# LEDs.net
KiCad netlist of a schematic drawn in Altium Designer
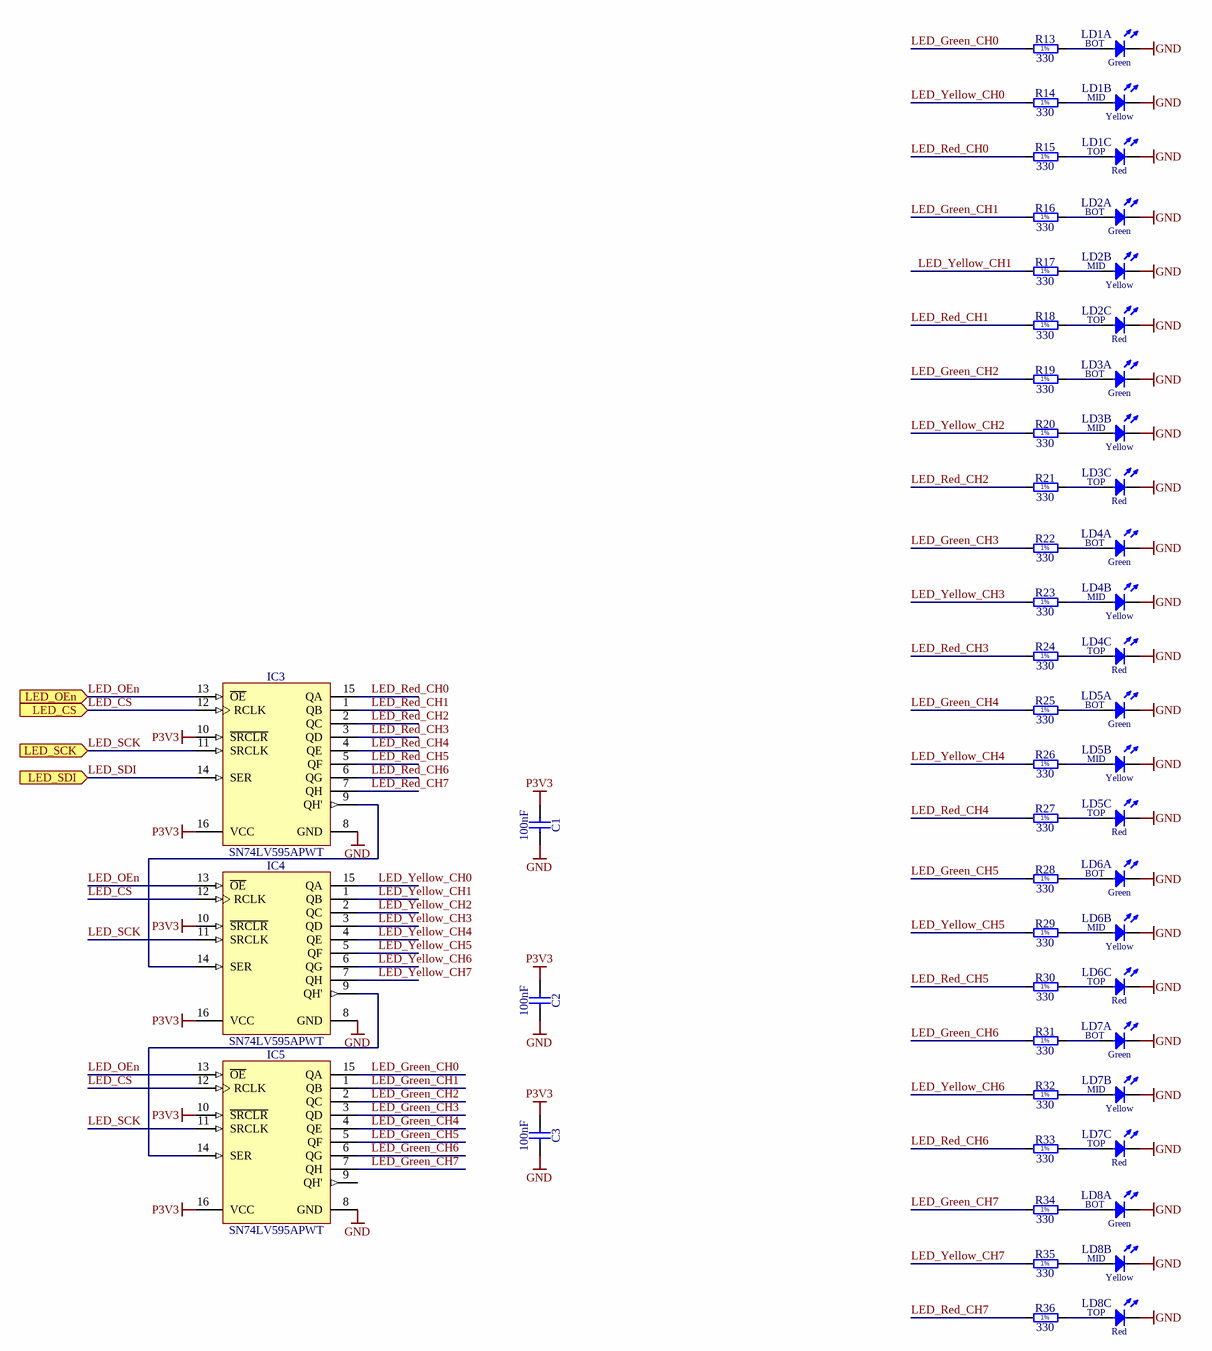
[diagram p0: LEDs.SchDoc]

(export (version "E")
  (design (tool "Eeschema 10.0.6"))
  (components
    (comp (ref "C1")
      (value "100nF")
      (footprint "CAPC1005X55N")
      (description "Non-polarised capacitor")
      (fields
        (field (name "PART NUMBER") "CC0402_100NF_16V_10%_X7R")
        (field (name "VOLTAGE") "16V")
        (field (name "AUTHOR") "CERN DEM JLC")
      )
      (libsource (lib "Capacitors") (part "Capacitor - non polarized"))
    )
    (comp (ref "C2")
      (value "100nF")
      (footprint "CAPC1005X55N")
      (description "Non-polarised capacitor")
      (fields
        (field (name "PART NUMBER") "CC0402_100NF_16V_10%_X7R")
        (field (name "VOLTAGE") "16V")
        (field (name "AUTHOR") "CERN DEM JLC")
      )
      (libsource (lib "Capacitors") (part "Capacitor - non polarized"))
    )
    (comp (ref "C3")
      (value "100nF")
      (footprint "CAPC1005X55N")
      (description "Non-polarised capacitor")
      (fields
        (field (name "PART NUMBER") "CC0402_100NF_16V_10%_X7R")
        (field (name "VOLTAGE") "16V")
        (field (name "AUTHOR") "CERN DEM JLC")
      )
      (libsource (lib "Capacitors") (part "Capacitor - non polarized"))
    )
    (comp (ref "IC3")
      (value "SN74LV595APWT")
      (footprint "SOP65P640X120-16N")
      (description "8-Bit Shift Register With 3-State Output Register")
      (fields (field (name "MANUFACTURER") "TEXAS INSTRUMENTS") (field (name "AUTHOR") "CERN DEM JLC"))
      (libsource (lib "ICs And Semiconductors") (part "74595"))
    )
    (comp (ref "IC4")
      (value "SN74LV595APWT")
      (footprint "SOP65P640X120-16N")
      (description "8-Bit Shift Register With 3-State Output Register")
      (fields (field (name "MANUFACTURER") "TEXAS INSTRUMENTS") (field (name "AUTHOR") "CERN DEM JLC"))
      (libsource (lib "ICs And Semiconductors") (part "74595"))
    )
    (comp (ref "IC5")
      (value "SN74LV595APWT")
      (footprint "SOP65P640X120-16N")
      (description "8-Bit Shift Register With 3-State Output Register")
      (fields (field (name "MANUFACTURER") "TEXAS INSTRUMENTS") (field (name "AUTHOR") "CERN DEM JLC"))
      (libsource (lib "ICs And Semiconductors") (part "74595"))
    )
    (comp (ref "LD1")
      (value "Red/Yellow/Green")
      (footprint "LED_MENTOR_1882.2781")
      (description "LED x3 G-1C2A-BOT_Y-3C4A_R-5C6A-TOP")
      (fields
        (field (name "PART NUMBER") "LED_MENTOR_1882.2781")
        (field (name "MANUFACTURER") "MENTOR")
        (field (name "AUTHOR") "CERN DEM JLC")
      )
      (libsource (lib "ICs And Semiconductors") (part "LED x3 G-1C2A-BOT_Y-3C4A_R-5C6A-TOP"))
    )
    (comp (ref "LD2")
      (value "Red/Yellow/Green")
      (footprint "LED_MENTOR_1882.2781")
      (description "LED x3 G-1C2A-BOT_Y-3C4A_R-5C6A-TOP")
      (fields
        (field (name "PART NUMBER") "LED_MENTOR_1882.2781")
        (field (name "MANUFACTURER") "MENTOR")
        (field (name "AUTHOR") "CERN DEM JLC")
      )
      (libsource (lib "ICs And Semiconductors") (part "LED x3 G-1C2A-BOT_Y-3C4A_R-5C6A-TOP"))
    )
    (comp (ref "LD3")
      (value "Red/Yellow/Green")
      (footprint "LED_MENTOR_1882.2781")
      (description "LED x3 G-1C2A-BOT_Y-3C4A_R-5C6A-TOP")
      (fields
        (field (name "PART NUMBER") "LED_MENTOR_1882.2781")
        (field (name "MANUFACTURER") "MENTOR")
        (field (name "AUTHOR") "CERN DEM JLC")
      )
      (libsource (lib "ICs And Semiconductors") (part "LED x3 G-1C2A-BOT_Y-3C4A_R-5C6A-TOP"))
    )
    (comp (ref "LD4")
      (value "Red/Yellow/Green")
      (footprint "LED_MENTOR_1882.2781")
      (description "LED x3 G-1C2A-BOT_Y-3C4A_R-5C6A-TOP")
      (fields
        (field (name "PART NUMBER") "LED_MENTOR_1882.2781")
        (field (name "MANUFACTURER") "MENTOR")
        (field (name "AUTHOR") "CERN DEM JLC")
      )
      (libsource (lib "ICs And Semiconductors") (part "LED x3 G-1C2A-BOT_Y-3C4A_R-5C6A-TOP"))
    )
    (comp (ref "LD5")
      (value "Red/Yellow/Green")
      (footprint "LED_MENTOR_1882.2781")
      (description "LED x3 G-1C2A-BOT_Y-3C4A_R-5C6A-TOP")
      (fields
        (field (name "PART NUMBER") "LED_MENTOR_1882.2781")
        (field (name "MANUFACTURER") "MENTOR")
        (field (name "AUTHOR") "CERN DEM JLC")
      )
      (libsource (lib "ICs And Semiconductors") (part "LED x3 G-1C2A-BOT_Y-3C4A_R-5C6A-TOP"))
    )
    (comp (ref "LD6")
      (value "Red/Yellow/Green")
      (footprint "LED_MENTOR_1882.2781")
      (description "LED x3 G-1C2A-BOT_Y-3C4A_R-5C6A-TOP")
      (fields
        (field (name "PART NUMBER") "LED_MENTOR_1882.2781")
        (field (name "MANUFACTURER") "MENTOR")
        (field (name "AUTHOR") "CERN DEM JLC")
      )
      (libsource (lib "ICs And Semiconductors") (part "LED x3 G-1C2A-BOT_Y-3C4A_R-5C6A-TOP"))
    )
    (comp (ref "LD7")
      (value "Red/Yellow/Green")
      (footprint "LED_MENTOR_1882.2781")
      (description "LED x3 G-1C2A-BOT_Y-3C4A_R-5C6A-TOP")
      (fields
        (field (name "PART NUMBER") "LED_MENTOR_1882.2781")
        (field (name "MANUFACTURER") "MENTOR")
        (field (name "AUTHOR") "CERN DEM JLC")
      )
      (libsource (lib "ICs And Semiconductors") (part "LED x3 G-1C2A-BOT_Y-3C4A_R-5C6A-TOP"))
    )
    (comp (ref "LD8")
      (value "Red/Yellow/Green")
      (footprint "LED_MENTOR_1882.2781")
      (description "LED x3 G-1C2A-BOT_Y-3C4A_R-5C6A-TOP")
      (fields
        (field (name "PART NUMBER") "LED_MENTOR_1882.2781")
        (field (name "MANUFACTURER") "MENTOR")
        (field (name "AUTHOR") "CERN DEM JLC")
      )
      (libsource (lib "ICs And Semiconductors") (part "LED x3 G-1C2A-BOT_Y-3C4A_R-5C6A-TOP"))
    )
    (comp (ref "R13")
      (value "330")
      (footprint "RESC1608X55N")
      (description "Resistor - 1%")
      (fields
        (field (name "PART NUMBER") "R0603_330R_1%_0.1W_100PPM")
        (field (name "POWER") "0.1W")
        (field (name "AUTHOR") "CERN DEM JLC")
      )
      (libsource (lib "Resistors") (part "Resistor - 1%"))
    )
    (comp (ref "R14")
      (value "330")
      (footprint "RESC1608X55N")
      (description "Resistor - 1%")
      (fields
        (field (name "PART NUMBER") "R0603_330R_1%_0.1W_100PPM")
        (field (name "POWER") "0.1W")
        (field (name "AUTHOR") "CERN DEM JLC")
      )
      (libsource (lib "Resistors") (part "Resistor - 1%"))
    )
    (comp (ref "R15")
      (value "330")
      (footprint "RESC1608X55N")
      (description "Resistor - 1%")
      (fields
        (field (name "PART NUMBER") "R0603_330R_1%_0.1W_100PPM")
        (field (name "POWER") "0.1W")
        (field (name "AUTHOR") "CERN DEM JLC")
      )
      (libsource (lib "Resistors") (part "Resistor - 1%"))
    )
    (comp (ref "R16")
      (value "330")
      (footprint "RESC1608X55N")
      (description "Resistor - 1%")
      (fields
        (field (name "PART NUMBER") "R0603_330R_1%_0.1W_100PPM")
        (field (name "POWER") "0.1W")
        (field (name "AUTHOR") "CERN DEM JLC")
      )
      (libsource (lib "Resistors") (part "Resistor - 1%"))
    )
    (comp (ref "R17")
      (value "330")
      (footprint "RESC1608X55N")
      (description "Resistor - 1%")
      (fields
        (field (name "PART NUMBER") "R0603_330R_1%_0.1W_100PPM")
        (field (name "POWER") "0.1W")
        (field (name "AUTHOR") "CERN DEM JLC")
      )
      (libsource (lib "Resistors") (part "Resistor - 1%"))
    )
    (comp (ref "R18")
      (value "330")
      (footprint "RESC1608X55N")
      (description "Resistor - 1%")
      (fields
        (field (name "PART NUMBER") "R0603_330R_1%_0.1W_100PPM")
        (field (name "POWER") "0.1W")
        (field (name "AUTHOR") "CERN DEM JLC")
      )
      (libsource (lib "Resistors") (part "Resistor - 1%"))
    )
    (comp (ref "R19")
      (value "330")
      (footprint "RESC1608X55N")
      (description "Resistor - 1%")
      (fields
        (field (name "PART NUMBER") "R0603_330R_1%_0.1W_100PPM")
        (field (name "POWER") "0.1W")
        (field (name "AUTHOR") "CERN DEM JLC")
      )
      (libsource (lib "Resistors") (part "Resistor - 1%"))
    )
    (comp (ref "R20")
      (value "330")
      (footprint "RESC1608X55N")
      (description "Resistor - 1%")
      (fields
        (field (name "PART NUMBER") "R0603_330R_1%_0.1W_100PPM")
        (field (name "POWER") "0.1W")
        (field (name "AUTHOR") "CERN DEM JLC")
      )
      (libsource (lib "Resistors") (part "Resistor - 1%"))
    )
    (comp (ref "R21")
      (value "330")
      (footprint "RESC1608X55N")
      (description "Resistor - 1%")
      (fields
        (field (name "PART NUMBER") "R0603_330R_1%_0.1W_100PPM")
        (field (name "POWER") "0.1W")
        (field (name "AUTHOR") "CERN DEM JLC")
      )
      (libsource (lib "Resistors") (part "Resistor - 1%"))
    )
    (comp (ref "R22")
      (value "330")
      (footprint "RESC1608X55N")
      (description "Resistor - 1%")
      (fields
        (field (name "PART NUMBER") "R0603_330R_1%_0.1W_100PPM")
        (field (name "POWER") "0.1W")
        (field (name "AUTHOR") "CERN DEM JLC")
      )
      (libsource (lib "Resistors") (part "Resistor - 1%"))
    )
    (comp (ref "R23")
      (value "330")
      (footprint "RESC1608X55N")
      (description "Resistor - 1%")
      (fields
        (field (name "PART NUMBER") "R0603_330R_1%_0.1W_100PPM")
        (field (name "POWER") "0.1W")
        (field (name "AUTHOR") "CERN DEM JLC")
      )
      (libsource (lib "Resistors") (part "Resistor - 1%"))
    )
    (comp (ref "R24")
      (value "330")
      (footprint "RESC1608X55N")
      (description "Resistor - 1%")
      (fields
        (field (name "PART NUMBER") "R0603_330R_1%_0.1W_100PPM")
        (field (name "POWER") "0.1W")
        (field (name "AUTHOR") "CERN DEM JLC")
      )
      (libsource (lib "Resistors") (part "Resistor - 1%"))
    )
    (comp (ref "R25")
      (value "330")
      (footprint "RESC1608X55N")
      (description "Resistor - 1%")
      (fields
        (field (name "PART NUMBER") "R0603_330R_1%_0.1W_100PPM")
        (field (name "POWER") "0.1W")
        (field (name "AUTHOR") "CERN DEM JLC")
      )
      (libsource (lib "Resistors") (part "Resistor - 1%"))
    )
    (comp (ref "R26")
      (value "330")
      (footprint "RESC1608X55N")
      (description "Resistor - 1%")
      (fields
        (field (name "PART NUMBER") "R0603_330R_1%_0.1W_100PPM")
        (field (name "POWER") "0.1W")
        (field (name "AUTHOR") "CERN DEM JLC")
      )
      (libsource (lib "Resistors") (part "Resistor - 1%"))
    )
    (comp (ref "R27")
      (value "330")
      (footprint "RESC1608X55N")
      (description "Resistor - 1%")
      (fields
        (field (name "PART NUMBER") "R0603_330R_1%_0.1W_100PPM")
        (field (name "POWER") "0.1W")
        (field (name "AUTHOR") "CERN DEM JLC")
      )
      (libsource (lib "Resistors") (part "Resistor - 1%"))
    )
    (comp (ref "R28")
      (value "330")
      (footprint "RESC1608X55N")
      (description "Resistor - 1%")
      (fields
        (field (name "PART NUMBER") "R0603_330R_1%_0.1W_100PPM")
        (field (name "POWER") "0.1W")
        (field (name "AUTHOR") "CERN DEM JLC")
      )
      (libsource (lib "Resistors") (part "Resistor - 1%"))
    )
    (comp (ref "R29")
      (value "330")
      (footprint "RESC1608X55N")
      (description "Resistor - 1%")
      (fields
        (field (name "PART NUMBER") "R0603_330R_1%_0.1W_100PPM")
        (field (name "POWER") "0.1W")
        (field (name "AUTHOR") "CERN DEM JLC")
      )
      (libsource (lib "Resistors") (part "Resistor - 1%"))
    )
    (comp (ref "R30")
      (value "330")
      (footprint "RESC1608X55N")
      (description "Resistor - 1%")
      (fields
        (field (name "PART NUMBER") "R0603_330R_1%_0.1W_100PPM")
        (field (name "POWER") "0.1W")
        (field (name "AUTHOR") "CERN DEM JLC")
      )
      (libsource (lib "Resistors") (part "Resistor - 1%"))
    )
    (comp (ref "R31")
      (value "330")
      (footprint "RESC1608X55N")
      (description "Resistor - 1%")
      (fields
        (field (name "PART NUMBER") "R0603_330R_1%_0.1W_100PPM")
        (field (name "POWER") "0.1W")
        (field (name "AUTHOR") "CERN DEM JLC")
      )
      (libsource (lib "Resistors") (part "Resistor - 1%"))
    )
    (comp (ref "R32")
      (value "330")
      (footprint "RESC1608X55N")
      (description "Resistor - 1%")
      (fields
        (field (name "PART NUMBER") "R0603_330R_1%_0.1W_100PPM")
        (field (name "POWER") "0.1W")
        (field (name "AUTHOR") "CERN DEM JLC")
      )
      (libsource (lib "Resistors") (part "Resistor - 1%"))
    )
    (comp (ref "R33")
      (value "330")
      (footprint "RESC1608X55N")
      (description "Resistor - 1%")
      (fields
        (field (name "PART NUMBER") "R0603_330R_1%_0.1W_100PPM")
        (field (name "POWER") "0.1W")
        (field (name "AUTHOR") "CERN DEM JLC")
      )
      (libsource (lib "Resistors") (part "Resistor - 1%"))
    )
    (comp (ref "R34")
      (value "330")
      (footprint "RESC1608X55N")
      (description "Resistor - 1%")
      (fields
        (field (name "PART NUMBER") "R0603_330R_1%_0.1W_100PPM")
        (field (name "POWER") "0.1W")
        (field (name "AUTHOR") "CERN DEM JLC")
      )
      (libsource (lib "Resistors") (part "Resistor - 1%"))
    )
    (comp (ref "R35")
      (value "330")
      (footprint "RESC1608X55N")
      (description "Resistor - 1%")
      (fields
        (field (name "PART NUMBER") "R0603_330R_1%_0.1W_100PPM")
        (field (name "POWER") "0.1W")
        (field (name "AUTHOR") "CERN DEM JLC")
      )
      (libsource (lib "Resistors") (part "Resistor - 1%"))
    )
    (comp (ref "R36")
      (value "330")
      (footprint "RESC1608X55N")
      (description "Resistor - 1%")
      (fields
        (field (name "PART NUMBER") "R0603_330R_1%_0.1W_100PPM")
        (field (name "POWER") "0.1W")
        (field (name "AUTHOR") "CERN DEM JLC")
      )
      (libsource (lib "Resistors") (part "Resistor - 1%"))
    )
  )
  (nets
    (net (code "1") (name "/LED_CS") (class "Default")
      (node (ref "IC3") (pin "12") (pinfunction "RCLK_12") (pintype "input"))
      (node (ref "IC4") (pin "12") (pinfunction "RCLK_12") (pintype "input"))
      (node (ref "IC5") (pin "12") (pinfunction "RCLK_12") (pintype "input"))
    )
    (net (code "2") (name "/LED_Green_CH0") (class "Default")
      (node (ref "IC5") (pin "15") (pinfunction "QA_15") (pintype "tri_state"))
      (node (ref "R13") (pin "1") (pinfunction "1_1") (pintype "passive"))
    )
    (net (code "3") (name "/LED_Green_CH1") (class "Default")
      (node (ref "IC5") (pin "1") (pinfunction "QB_1") (pintype "tri_state"))
      (node (ref "R16") (pin "1") (pinfunction "1_1") (pintype "passive"))
    )
    (net (code "4") (name "/LED_Green_CH2") (class "Default")
      (node (ref "IC5") (pin "2") (pinfunction "QC_2") (pintype "tri_state"))
      (node (ref "R19") (pin "1") (pinfunction "1_1") (pintype "passive"))
    )
    (net (code "5") (name "/LED_Green_CH3") (class "Default")
      (node (ref "IC5") (pin "3") (pinfunction "QD_3") (pintype "tri_state"))
      (node (ref "R22") (pin "1") (pinfunction "1_1") (pintype "passive"))
    )
    (net (code "6") (name "/LED_Green_CH4") (class "Default")
      (node (ref "IC5") (pin "4") (pinfunction "QE_4") (pintype "tri_state"))
      (node (ref "R25") (pin "1") (pinfunction "1_1") (pintype "passive"))
    )
    (net (code "7") (name "/LED_Green_CH5") (class "Default")
      (node (ref "IC5") (pin "5") (pinfunction "QF_5") (pintype "tri_state"))
      (node (ref "R28") (pin "1") (pinfunction "1_1") (pintype "passive"))
    )
    (net (code "8") (name "/LED_Green_CH6") (class "Default")
      (node (ref "IC5") (pin "6") (pinfunction "QG_6") (pintype "tri_state"))
      (node (ref "R31") (pin "1") (pinfunction "1_1") (pintype "passive"))
    )
    (net (code "9") (name "/LED_Green_CH7") (class "Default")
      (node (ref "IC5") (pin "7") (pinfunction "QH_7") (pintype "tri_state"))
      (node (ref "R34") (pin "1") (pinfunction "1_1") (pintype "passive"))
    )
    (net (code "10") (name "/LED_OEn") (class "Default")
      (node (ref "IC3") (pin "13") (pinfunction "~{OE}_13") (pintype "input"))
      (node (ref "IC4") (pin "13") (pinfunction "~{OE}_13") (pintype "input"))
      (node (ref "IC5") (pin "13") (pinfunction "~{OE}_13") (pintype "input"))
    )
    (net (code "11") (name "/LED_Red_CH0") (class "Default")
      (node (ref "IC3") (pin "15") (pinfunction "QA_15") (pintype "tri_state"))
      (node (ref "R15") (pin "1") (pinfunction "1_1") (pintype "passive"))
    )
    (net (code "12") (name "/LED_Red_CH1") (class "Default")
      (node (ref "IC3") (pin "1") (pinfunction "QB_1") (pintype "tri_state"))
      (node (ref "R18") (pin "1") (pinfunction "1_1") (pintype "passive"))
    )
    (net (code "13") (name "/LED_Red_CH2") (class "Default")
      (node (ref "IC3") (pin "2") (pinfunction "QC_2") (pintype "tri_state"))
      (node (ref "R21") (pin "1") (pinfunction "1_1") (pintype "passive"))
    )
    (net (code "14") (name "/LED_Red_CH3") (class "Default")
      (node (ref "IC3") (pin "3") (pinfunction "QD_3") (pintype "tri_state"))
      (node (ref "R24") (pin "1") (pinfunction "1_1") (pintype "passive"))
    )
    (net (code "15") (name "/LED_Red_CH4") (class "Default")
      (node (ref "IC3") (pin "4") (pinfunction "QE_4") (pintype "tri_state"))
      (node (ref "R27") (pin "1") (pinfunction "1_1") (pintype "passive"))
    )
    (net (code "16") (name "/LED_Red_CH5") (class "Default")
      (node (ref "IC3") (pin "5") (pinfunction "QF_5") (pintype "tri_state"))
      (node (ref "R30") (pin "1") (pinfunction "1_1") (pintype "passive"))
    )
    (net (code "17") (name "/LED_Red_CH6") (class "Default")
      (node (ref "IC3") (pin "6") (pinfunction "QG_6") (pintype "tri_state"))
      (node (ref "R33") (pin "1") (pinfunction "1_1") (pintype "passive"))
    )
    (net (code "18") (name "/LED_Red_CH7") (class "Default")
      (node (ref "IC3") (pin "7") (pinfunction "QH_7") (pintype "tri_state"))
      (node (ref "R36") (pin "1") (pinfunction "1_1") (pintype "passive"))
    )
    (net (code "19") (name "/LED_SCK") (class "Default")
      (node (ref "IC3") (pin "11") (pinfunction "SRCLK_11") (pintype "input"))
      (node (ref "IC4") (pin "11") (pinfunction "SRCLK_11") (pintype "input"))
      (node (ref "IC5") (pin "11") (pinfunction "SRCLK_11") (pintype "input"))
    )
    (net (code "20") (name "/LED_SDI") (class "Default")
      (node (ref "IC3") (pin "14") (pinfunction "SER_14") (pintype "input"))
    )
    (net (code "21") (name "/LED_Yellow_CH0") (class "Default")
      (node (ref "IC4") (pin "15") (pinfunction "QA_15") (pintype "tri_state"))
      (node (ref "R14") (pin "1") (pinfunction "1_1") (pintype "passive"))
    )
    (net (code "22") (name "/LED_Yellow_CH1") (class "Default")
      (node (ref "IC4") (pin "1") (pinfunction "QB_1") (pintype "tri_state"))
      (node (ref "R17") (pin "1") (pinfunction "1_1") (pintype "passive"))
    )
    (net (code "23") (name "/LED_Yellow_CH2") (class "Default")
      (node (ref "IC4") (pin "2") (pinfunction "QC_2") (pintype "tri_state"))
      (node (ref "R20") (pin "1") (pinfunction "1_1") (pintype "passive"))
    )
    (net (code "24") (name "/LED_Yellow_CH3") (class "Default")
      (node (ref "IC4") (pin "3") (pinfunction "QD_3") (pintype "tri_state"))
      (node (ref "R23") (pin "1") (pinfunction "1_1") (pintype "passive"))
    )
    (net (code "25") (name "/LED_Yellow_CH4") (class "Default")
      (node (ref "IC4") (pin "4") (pinfunction "QE_4") (pintype "tri_state"))
      (node (ref "R26") (pin "1") (pinfunction "1_1") (pintype "passive"))
    )
    (net (code "26") (name "/LED_Yellow_CH5") (class "Default")
      (node (ref "IC4") (pin "5") (pinfunction "QF_5") (pintype "tri_state"))
      (node (ref "R29") (pin "1") (pinfunction "1_1") (pintype "passive"))
    )
    (net (code "27") (name "/LED_Yellow_CH6") (class "Default")
      (node (ref "IC4") (pin "6") (pinfunction "QG_6") (pintype "tri_state"))
      (node (ref "R32") (pin "1") (pinfunction "1_1") (pintype "passive"))
    )
    (net (code "28") (name "/LED_Yellow_CH7") (class "Default")
      (node (ref "IC4") (pin "7") (pinfunction "QH_7") (pintype "tri_state"))
      (node (ref "R35") (pin "1") (pinfunction "1_1") (pintype "passive"))
    )
    (net (code "29") (name "GND") (class "Default")
      (node (ref "C1") (pin "2") (pinfunction "2_2") (pintype "passive"))
      (node (ref "C2") (pin "2") (pinfunction "2_2") (pintype "passive"))
      (node (ref "C3") (pin "2") (pinfunction "2_2") (pintype "passive"))
      (node (ref "IC3") (pin "8") (pinfunction "GND_8") (pintype "power_in"))
      (node (ref "IC4") (pin "8") (pinfunction "GND_8") (pintype "power_in"))
      (node (ref "IC5") (pin "8") (pinfunction "GND_8") (pintype "power_in"))
      (node (ref "LD1") (pin "1") (pinfunction "C_1") (pintype "passive"))
      (node (ref "LD1") (pin "3") (pinfunction "C_3") (pintype "passive"))
      (node (ref "LD1") (pin "5") (pinfunction "C_5") (pintype "passive"))
      (node (ref "LD2") (pin "1") (pinfunction "C_1") (pintype "passive"))
      (node (ref "LD2") (pin "3") (pinfunction "C_3") (pintype "passive"))
      (node (ref "LD2") (pin "5") (pinfunction "C_5") (pintype "passive"))
      (node (ref "LD3") (pin "1") (pinfunction "C_1") (pintype "passive"))
      (node (ref "LD3") (pin "3") (pinfunction "C_3") (pintype "passive"))
      (node (ref "LD3") (pin "5") (pinfunction "C_5") (pintype "passive"))
      (node (ref "LD4") (pin "1") (pinfunction "C_1") (pintype "passive"))
      (node (ref "LD4") (pin "3") (pinfunction "C_3") (pintype "passive"))
      (node (ref "LD4") (pin "5") (pinfunction "C_5") (pintype "passive"))
      (node (ref "LD5") (pin "1") (pinfunction "C_1") (pintype "passive"))
      (node (ref "LD5") (pin "3") (pinfunction "C_3") (pintype "passive"))
      (node (ref "LD5") (pin "5") (pinfunction "C_5") (pintype "passive"))
      (node (ref "LD6") (pin "1") (pinfunction "C_1") (pintype "passive"))
      (node (ref "LD6") (pin "3") (pinfunction "C_3") (pintype "passive"))
      (node (ref "LD6") (pin "5") (pinfunction "C_5") (pintype "passive"))
      (node (ref "LD7") (pin "1") (pinfunction "C_1") (pintype "passive"))
      (node (ref "LD7") (pin "3") (pinfunction "C_3") (pintype "passive"))
      (node (ref "LD7") (pin "5") (pinfunction "C_5") (pintype "passive"))
      (node (ref "LD8") (pin "1") (pinfunction "C_1") (pintype "passive"))
      (node (ref "LD8") (pin "3") (pinfunction "C_3") (pintype "passive"))
      (node (ref "LD8") (pin "5") (pinfunction "C_5") (pintype "passive"))
    )
    (net (code "30") (name "Net-(IC3-QH')") (class "Default")
      (node (ref "IC3") (pin "9") (pinfunction "QH'_9") (pintype "output"))
      (node (ref "IC4") (pin "14") (pinfunction "SER_14") (pintype "input"))
    )
    (net (code "31") (name "Net-(IC4-QH')") (class "Default")
      (node (ref "IC4") (pin "9") (pinfunction "QH'_9") (pintype "output"))
      (node (ref "IC5") (pin "14") (pinfunction "SER_14") (pintype "input"))
    )
    (net (code "32") (name "Net-(LD1A-A)") (class "Default")
      (node (ref "LD1") (pin "2") (pinfunction "A_2") (pintype "passive"))
      (node (ref "R13") (pin "2") (pinfunction "2_2") (pintype "passive"))
    )
    (net (code "33") (name "Net-(LD1B-A)") (class "Default")
      (node (ref "LD1") (pin "4") (pinfunction "A_4") (pintype "passive"))
      (node (ref "R14") (pin "2") (pinfunction "2_2") (pintype "passive"))
    )
    (net (code "34") (name "Net-(LD1C-A)") (class "Default")
      (node (ref "LD1") (pin "6") (pinfunction "A_6") (pintype "passive"))
      (node (ref "R15") (pin "2") (pinfunction "2_2") (pintype "passive"))
    )
    (net (code "35") (name "Net-(LD2A-A)") (class "Default")
      (node (ref "LD2") (pin "2") (pinfunction "A_2") (pintype "passive"))
      (node (ref "R16") (pin "2") (pinfunction "2_2") (pintype "passive"))
    )
    (net (code "36") (name "Net-(LD2B-A)") (class "Default")
      (node (ref "LD2") (pin "4") (pinfunction "A_4") (pintype "passive"))
      (node (ref "R17") (pin "2") (pinfunction "2_2") (pintype "passive"))
    )
    (net (code "37") (name "Net-(LD2C-A)") (class "Default")
      (node (ref "LD2") (pin "6") (pinfunction "A_6") (pintype "passive"))
      (node (ref "R18") (pin "2") (pinfunction "2_2") (pintype "passive"))
    )
    (net (code "38") (name "Net-(LD3A-A)") (class "Default")
      (node (ref "LD3") (pin "2") (pinfunction "A_2") (pintype "passive"))
      (node (ref "R19") (pin "2") (pinfunction "2_2") (pintype "passive"))
    )
    (net (code "39") (name "Net-(LD3B-A)") (class "Default")
      (node (ref "LD3") (pin "4") (pinfunction "A_4") (pintype "passive"))
      (node (ref "R20") (pin "2") (pinfunction "2_2") (pintype "passive"))
    )
    (net (code "40") (name "Net-(LD3C-A)") (class "Default")
      (node (ref "LD3") (pin "6") (pinfunction "A_6") (pintype "passive"))
      (node (ref "R21") (pin "2") (pinfunction "2_2") (pintype "passive"))
    )
    (net (code "41") (name "Net-(LD4A-A)") (class "Default")
      (node (ref "LD4") (pin "2") (pinfunction "A_2") (pintype "passive"))
      (node (ref "R22") (pin "2") (pinfunction "2_2") (pintype "passive"))
    )
    (net (code "42") (name "Net-(LD4B-A)") (class "Default")
      (node (ref "LD4") (pin "4") (pinfunction "A_4") (pintype "passive"))
      (node (ref "R23") (pin "2") (pinfunction "2_2") (pintype "passive"))
    )
    (net (code "43") (name "Net-(LD4C-A)") (class "Default")
      (node (ref "LD4") (pin "6") (pinfunction "A_6") (pintype "passive"))
      (node (ref "R24") (pin "2") (pinfunction "2_2") (pintype "passive"))
    )
    (net (code "44") (name "Net-(LD5A-A)") (class "Default")
      (node (ref "LD5") (pin "2") (pinfunction "A_2") (pintype "passive"))
      (node (ref "R25") (pin "2") (pinfunction "2_2") (pintype "passive"))
    )
    (net (code "45") (name "Net-(LD5B-A)") (class "Default")
      (node (ref "LD5") (pin "4") (pinfunction "A_4") (pintype "passive"))
      (node (ref "R26") (pin "2") (pinfunction "2_2") (pintype "passive"))
    )
    (net (code "46") (name "Net-(LD5C-A)") (class "Default")
      (node (ref "LD5") (pin "6") (pinfunction "A_6") (pintype "passive"))
      (node (ref "R27") (pin "2") (pinfunction "2_2") (pintype "passive"))
    )
    (net (code "47") (name "Net-(LD6A-A)") (class "Default")
      (node (ref "LD6") (pin "2") (pinfunction "A_2") (pintype "passive"))
      (node (ref "R28") (pin "2") (pinfunction "2_2") (pintype "passive"))
    )
    (net (code "48") (name "Net-(LD6B-A)") (class "Default")
      (node (ref "LD6") (pin "4") (pinfunction "A_4") (pintype "passive"))
      (node (ref "R29") (pin "2") (pinfunction "2_2") (pintype "passive"))
    )
    (net (code "49") (name "Net-(LD6C-A)") (class "Default")
      (node (ref "LD6") (pin "6") (pinfunction "A_6") (pintype "passive"))
      (node (ref "R30") (pin "2") (pinfunction "2_2") (pintype "passive"))
    )
    (net (code "50") (name "Net-(LD7A-A)") (class "Default")
      (node (ref "LD7") (pin "2") (pinfunction "A_2") (pintype "passive"))
      (node (ref "R31") (pin "2") (pinfunction "2_2") (pintype "passive"))
    )
    (net (code "51") (name "Net-(LD7B-A)") (class "Default")
      (node (ref "LD7") (pin "4") (pinfunction "A_4") (pintype "passive"))
      (node (ref "R32") (pin "2") (pinfunction "2_2") (pintype "passive"))
    )
    (net (code "52") (name "Net-(LD7C-A)") (class "Default")
      (node (ref "LD7") (pin "6") (pinfunction "A_6") (pintype "passive"))
      (node (ref "R33") (pin "2") (pinfunction "2_2") (pintype "passive"))
    )
    (net (code "53") (name "Net-(LD8A-A)") (class "Default")
      (node (ref "LD8") (pin "2") (pinfunction "A_2") (pintype "passive"))
      (node (ref "R34") (pin "2") (pinfunction "2_2") (pintype "passive"))
    )
    (net (code "54") (name "Net-(LD8B-A)") (class "Default")
      (node (ref "LD8") (pin "4") (pinfunction "A_4") (pintype "passive"))
      (node (ref "R35") (pin "2") (pinfunction "2_2") (pintype "passive"))
    )
    (net (code "55") (name "Net-(LD8C-A)") (class "Default")
      (node (ref "LD8") (pin "6") (pinfunction "A_6") (pintype "passive"))
      (node (ref "R36") (pin "2") (pinfunction "2_2") (pintype "passive"))
    )
    (net (code "56") (name "P3V3") (class "Default")
      (node (ref "C1") (pin "1") (pinfunction "1_1") (pintype "passive"))
      (node (ref "C2") (pin "1") (pinfunction "1_1") (pintype "passive"))
      (node (ref "C3") (pin "1") (pinfunction "1_1") (pintype "passive"))
      (node (ref "IC3") (pin "10") (pinfunction "~{SRCLR}_10") (pintype "input"))
      (node (ref "IC3") (pin "16") (pinfunction "VCC_16") (pintype "power_in"))
      (node (ref "IC4") (pin "10") (pinfunction "~{SRCLR}_10") (pintype "input"))
      (node (ref "IC4") (pin "16") (pinfunction "VCC_16") (pintype "power_in"))
      (node (ref "IC5") (pin "10") (pinfunction "~{SRCLR}_10") (pintype "input"))
      (node (ref "IC5") (pin "16") (pinfunction "VCC_16") (pintype "power_in"))
    )
    (net (code "57") (name "unconnected-(IC5-QH'-Pad9)") (class "Default")
      (node (ref "IC5") (pin "9") (pinfunction "QH'_9") (pintype "output"))
    )
  )
)
